# DM2080_Connector_B.net
KiCad netlist of a schematic drawn in Altium Designer
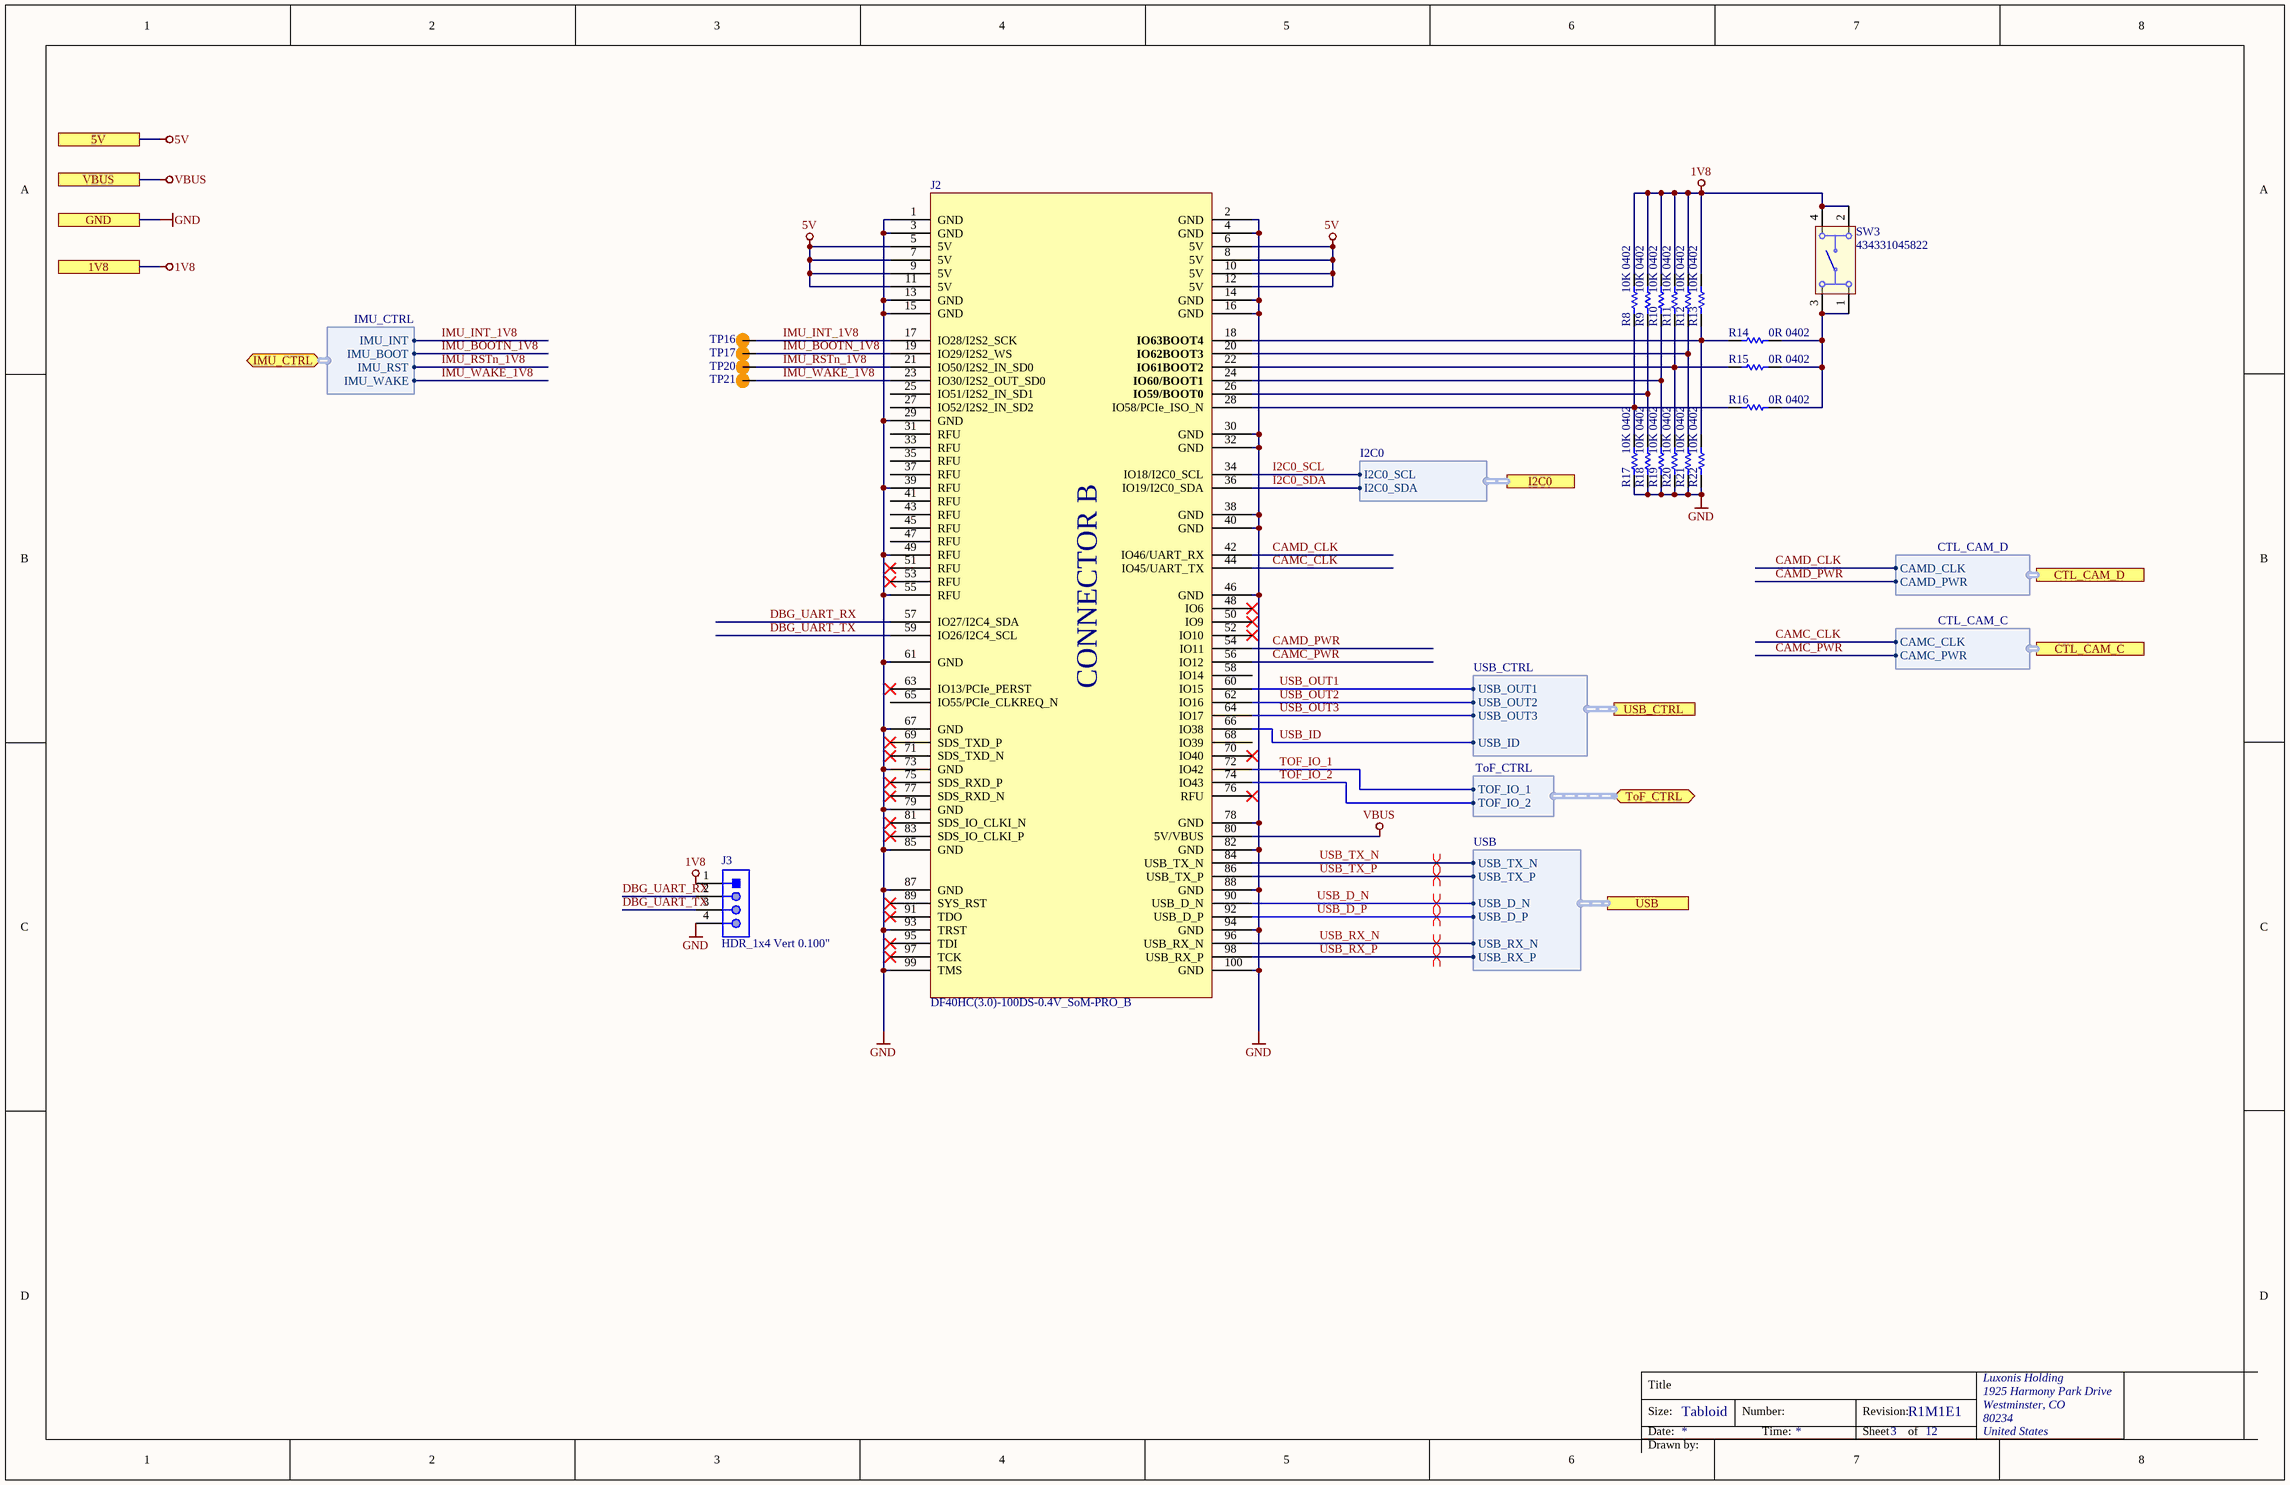
[diagram p0: DM2080_Connector_B.SchDoc]

(export (version "E")
  (design (tool "Eeschema 10.0.6"))
  (components
    (comp (ref "J2")
      (value "DF40HC(3.0)-100DS-0.4V_SoM-PRO_B")
      (footprint "CON_B_BW2099_SoM_DF40HC-3.0-100DS-0.4V_minpad")
      (description "OAK-SoM-Pro base board conn. B")
      (libsource (lib "Luxonis LLC") (part "DF40HC(3.0)-100DS-0.4V_SoM-PRO_B"))
    )
    (comp (ref "J3")
      (value "HDR_1x4 Vert 0.100\"")
      (footprint "LuxonisMaster:61300411121")
      (description "CONN HEADER VERT 4POS 2.54MM  Connector Header Through Hole 4 position 0.100\" (2.54mm)")
      (libsource (lib "LuxonisMaster") (part "61300411121"))
    )
    (comp (ref "R8")
      (value "10K 0402")
      (footprint "RES_Altium_Vault_Generic:RESC0402(1005)_L")
      (fields (field (name "TOLERANCE") "1%"))
      (libsource (lib "LuxonisMaster") (part "RC0402FR-1310KL"))
    )
    (comp (ref "R9")
      (value "10K 0402")
      (footprint "RES_Altium_Vault_Generic:RESC0402(1005)_L")
      (fields (field (name "TOLERANCE") "1%"))
      (libsource (lib "LuxonisMaster") (part "RC0402FR-1310KL"))
    )
    (comp (ref "R10")
      (value "10K 0402")
      (footprint "RES_Altium_Vault_Generic:RESC0402(1005)_L")
      (fields (field (name "TOLERANCE") "1%"))
      (libsource (lib "LuxonisMaster") (part "RC0402FR-1310KL"))
    )
    (comp (ref "R11")
      (value "10K 0402")
      (footprint "RES_Altium_Vault_Generic:RESC0402(1005)_L")
      (fields (field (name "TOLERANCE") "1%"))
      (libsource (lib "LuxonisMaster") (part "RC0402FR-1310KL"))
    )
    (comp (ref "R12")
      (value "10K 0402")
      (footprint "RES_Altium_Vault_Generic:RESC0402(1005)_L")
      (fields (field (name "TOLERANCE") "1%"))
      (libsource (lib "LuxonisMaster") (part "RC0402FR-1310KL"))
    )
    (comp (ref "R13")
      (value "10K 0402")
      (footprint "RES_Altium_Vault_Generic:RESC0402(1005)_L")
      (fields (field (name "TOLERANCE") "1%"))
      (libsource (lib "LuxonisMaster") (part "RC0402FR-1310KL"))
    )
    (comp (ref "R14")
      (value "0R 0402")
      (footprint "RES_Altium_Vault_Generic:RESC0402(1005)_L")
      (description "RES SMD 0 OHM JUMPER 1/16W 0402")
      (fields (field (name "TOLERANCE") "5%"))
      (libsource (lib "LuxonisMaster") (part "CRCW04020000Z0ED"))
    )
    (comp (ref "R15")
      (value "0R 0402")
      (footprint "RES_Altium_Vault_Generic:RESC0402(1005)_L")
      (description "RES SMD 0 OHM JUMPER 1/16W 0402")
      (fields (field (name "TOLERANCE") "5%"))
      (libsource (lib "LuxonisMaster") (part "CRCW04020000Z0ED"))
    )
    (comp (ref "R16")
      (value "0R 0402")
      (footprint "RES_Altium_Vault_Generic:RESC0402(1005)_L")
      (description "RES SMD 0 OHM JUMPER 1/16W 0402")
      (fields (field (name "TOLERANCE") "5%"))
      (libsource (lib "LuxonisMaster") (part "CRCW04020000Z0ED"))
    )
    (comp (ref "R17")
      (value "10K 0402")
      (footprint "RES_Altium_Vault_Generic:RESC0402(1005)_L")
      (fields (field (name "TOLERANCE") "1%"))
      (libsource (lib "LuxonisMaster") (part "RC0402FR-1310KL"))
    )
    (comp (ref "R18")
      (value "10K 0402")
      (footprint "RES_Altium_Vault_Generic:RESC0402(1005)_L")
      (fields (field (name "TOLERANCE") "1%"))
      (libsource (lib "LuxonisMaster") (part "RC0402FR-1310KL"))
    )
    (comp (ref "R19")
      (value "10K 0402")
      (footprint "RES_Altium_Vault_Generic:RESC0402(1005)_L")
      (fields (field (name "TOLERANCE") "1%"))
      (libsource (lib "LuxonisMaster") (part "RC0402FR-1310KL"))
    )
    (comp (ref "R20")
      (value "10K 0402")
      (footprint "RES_Altium_Vault_Generic:RESC0402(1005)_L")
      (fields (field (name "TOLERANCE") "1%"))
      (libsource (lib "LuxonisMaster") (part "RC0402FR-1310KL"))
    )
    (comp (ref "R21")
      (value "10K 0402")
      (footprint "RES_Altium_Vault_Generic:RESC0402(1005)_L")
      (fields (field (name "TOLERANCE") "1%"))
      (libsource (lib "LuxonisMaster") (part "RC0402FR-1310KL"))
    )
    (comp (ref "R22")
      (value "10K 0402")
      (footprint "RES_Altium_Vault_Generic:RESC0402(1005)_L")
      (fields (field (name "TOLERANCE") "1%"))
      (libsource (lib "LuxonisMaster") (part "RC0402FR-1310KL"))
    )
    (comp (ref "SW3")
      (value "434331045822")
      (footprint "434331045822")
      (libsource (lib "Luxonis LLC") (part "WE-TACT-SW-4"))
    )
    (comp (ref "TP16")
      (value "TP100_200_NS")
      (footprint "LuxonisMaster:TP100_200_NS")
      (libsource (lib "LuxonisMaster") (part "TEST_POINT"))
    )
    (comp (ref "TP17")
      (value "TP100_200_NS")
      (footprint "LuxonisMaster:TP100_200_NS")
      (libsource (lib "LuxonisMaster") (part "TEST_POINT"))
    )
    (comp (ref "TP20")
      (value "TP100_200_NS")
      (footprint "LuxonisMaster:TP100_200_NS")
      (libsource (lib "LuxonisMaster") (part "TEST_POINT"))
    )
    (comp (ref "TP21")
      (value "TP100_200_NS")
      (footprint "LuxonisMaster:TP100_200_NS")
      (libsource (lib "LuxonisMaster") (part "TEST_POINT"))
    )
  )
  (nets
    (net (code "8") (name "/CAMC_CLK") (class "Default")
      (node (ref "J2") (pin "44") (pinfunction "IO45/UART_TX_44") (pintype "passive"))
    )
    (net (code "9") (name "/CAMC_PWR") (class "Default")
      (node (ref "J2") (pin "56") (pinfunction "IO12_56") (pintype "passive"))
    )
    (net (code "10") (name "/CAMD_CLK") (class "Default")
      (node (ref "J2") (pin "42") (pinfunction "IO46/UART_RX_42") (pintype "passive"))
    )
    (net (code "11") (name "/CAMD_PWR") (class "Default")
      (node (ref "J2") (pin "54") (pinfunction "IO11_54") (pintype "passive"))
    )
    (net (code "12") (name "/DBG_UART_RX") (class "Default")
      (node (ref "J2") (pin "57") (pinfunction "IO27/I2C4_SDA_57") (pintype "passive"))
      (node (ref "J3") (pin "2") (pinfunction "2_2") (pintype "passive"))
    )
    (net (code "13") (name "/DBG_UART_TX") (class "Default")
      (node (ref "J2") (pin "59") (pinfunction "IO26/I2C4_SCL_59") (pintype "passive"))
      (node (ref "J3") (pin "3") (pinfunction "3_3") (pintype "passive"))
    )
    (net (code "14") (name "/I2C0_SCL") (class "Default")
      (node (ref "J2") (pin "34") (pinfunction "IO18/I2C0_SCL_34") (pintype "passive"))
    )
    (net (code "15") (name "/I2C0_SDA") (class "Default")
      (node (ref "J2") (pin "36") (pinfunction "IO19/I2C0_SDA_36") (pintype "passive"))
    )
    (net (code "16") (name "/IMU_BOOTN_1V8") (class "Default")
      (node (ref "J2") (pin "19") (pinfunction "IO29/I2S2_WS_19") (pintype "passive"))
      (node (ref "TP17") (pin "1") (pintype "passive"))
    )
    (net (code "17") (name "/IMU_INT_1V8") (class "Default")
      (node (ref "J2") (pin "17") (pinfunction "IO28/I2S2_SCK_17") (pintype "passive"))
      (node (ref "TP16") (pin "1") (pintype "passive"))
    )
    (net (code "18") (name "/IMU_RSTn_1V8") (class "Default")
      (node (ref "J2") (pin "21") (pinfunction "IO50/I2S2_IN_SD0_21") (pintype "passive"))
      (node (ref "TP20") (pin "1") (pintype "passive"))
    )
    (net (code "19") (name "/IMU_WAKE_1V8") (class "Default")
      (node (ref "J2") (pin "23") (pinfunction "IO30/I2S2_OUT_SD0_23") (pintype "passive"))
      (node (ref "TP21") (pin "1") (pintype "passive"))
    )
    (net (code "20") (name "/TOF_IO_1") (class "Default")
      (node (ref "J2") (pin "72") (pinfunction "IO42_72") (pintype "passive"))
    )
    (net (code "21") (name "/TOF_IO_2") (class "Default")
      (node (ref "J2") (pin "74") (pinfunction "IO43_74") (pintype "passive"))
    )
    (net (code "22") (name "/USB_D_N") (class "Default")
      (node (ref "J2") (pin "90") (pinfunction "USB_D_N_90") (pintype "passive"))
    )
    (net (code "23") (name "/USB_D_P") (class "Default")
      (node (ref "J2") (pin "92") (pinfunction "USB_D_P_92") (pintype "passive"))
    )
    (net (code "24") (name "/USB_ID") (class "Default")
      (node (ref "J2") (pin "66") (pinfunction "IO38_66") (pintype "passive"))
    )
    (net (code "25") (name "/USB_OUT1") (class "Default")
      (node (ref "J2") (pin "60") (pinfunction "IO15_60") (pintype "passive"))
    )
    (net (code "26") (name "/USB_OUT2") (class "Default")
      (node (ref "J2") (pin "62") (pinfunction "IO16_62") (pintype "passive"))
    )
    (net (code "27") (name "/USB_OUT3") (class "Default")
      (node (ref "J2") (pin "64") (pinfunction "IO17_64") (pintype "passive"))
    )
    (net (code "28") (name "/USB_RX_N") (class "Default")
      (node (ref "J2") (pin "96") (pinfunction "USB_RX_N_96") (pintype "passive"))
    )
    (net (code "29") (name "/USB_RX_P") (class "Default")
      (node (ref "J2") (pin "98") (pinfunction "USB_RX_P_98") (pintype "passive"))
    )
    (net (code "30") (name "/USB_TX_N") (class "Default")
      (node (ref "J2") (pin "84") (pinfunction "USB_TX_N_84") (pintype "passive"))
    )
    (net (code "31") (name "/USB_TX_P") (class "Default")
      (node (ref "J2") (pin "86") (pinfunction "USB_TX_P_86") (pintype "passive"))
    )
    (net (code "39") (name "1V8") (class "Default")
      (node (ref "J3") (pin "1") (pinfunction "1_1") (pintype "passive"))
      (node (ref "R10") (pin "2") (pinfunction "2_2") (pintype "passive"))
      (node (ref "R11") (pin "2") (pinfunction "2_2") (pintype "passive"))
      (node (ref "R12") (pin "2") (pinfunction "2_2") (pintype "passive"))
      (node (ref "R13") (pin "2") (pinfunction "2_2") (pintype "passive"))
      (node (ref "R8") (pin "2") (pinfunction "2_2") (pintype "passive"))
      (node (ref "R9") (pin "2") (pinfunction "2_2") (pintype "passive"))
      (node (ref "SW3") (pin "2") (pinfunction "2_2") (pintype "passive"))
      (node (ref "SW3") (pin "4") (pinfunction "4_4") (pintype "passive"))
    )
    (net (code "40") (name "5V") (class "Default")
      (node (ref "J2") (pin "10") (pinfunction "5V_10") (pintype "passive"))
      (node (ref "J2") (pin "11") (pinfunction "5V_11") (pintype "passive"))
      (node (ref "J2") (pin "12") (pinfunction "5V_12") (pintype "passive"))
      (node (ref "J2") (pin "5") (pinfunction "5V_5") (pintype "passive"))
      (node (ref "J2") (pin "6") (pinfunction "5V_6") (pintype "passive"))
      (node (ref "J2") (pin "7") (pinfunction "5V_7") (pintype "passive"))
      (node (ref "J2") (pin "8") (pinfunction "5V_8") (pintype "passive"))
      (node (ref "J2") (pin "9") (pinfunction "5V_9") (pintype "passive"))
    )
    (net (code "41") (name "GND") (class "Default")
      (node (ref "J2") (pin "1") (pinfunction "GND_1") (pintype "passive"))
      (node (ref "J2") (pin "100") (pinfunction "GND_100") (pintype "passive"))
      (node (ref "J2") (pin "13") (pinfunction "GND_13") (pintype "passive"))
      (node (ref "J2") (pin "14") (pinfunction "GND_14") (pintype "passive"))
      (node (ref "J2") (pin "15") (pinfunction "GND_15") (pintype "passive"))
      (node (ref "J2") (pin "16") (pinfunction "GND_16") (pintype "passive"))
      (node (ref "J2") (pin "2") (pinfunction "GND_2") (pintype "passive"))
      (node (ref "J2") (pin "29") (pinfunction "GND_29") (pintype "passive"))
      (node (ref "J2") (pin "3") (pinfunction "GND_3") (pintype "passive"))
      (node (ref "J2") (pin "30") (pinfunction "GND_30") (pintype "passive"))
      (node (ref "J2") (pin "32") (pinfunction "GND_32") (pintype "passive"))
      (node (ref "J2") (pin "38") (pinfunction "GND_38") (pintype "passive"))
      (node (ref "J2") (pin "39") (pinfunction "RFU_39") (pintype "passive"))
      (node (ref "J2") (pin "4") (pinfunction "GND_4") (pintype "passive"))
      (node (ref "J2") (pin "40") (pinfunction "GND_40") (pintype "passive"))
      (node (ref "J2") (pin "46") (pinfunction "GND_46") (pintype "passive"))
      (node (ref "J2") (pin "49") (pinfunction "RFU_49") (pintype "passive"))
      (node (ref "J2") (pin "55") (pinfunction "RFU_55") (pintype "passive"))
      (node (ref "J2") (pin "61") (pinfunction "GND_61") (pintype "passive"))
      (node (ref "J2") (pin "67") (pinfunction "GND_67") (pintype "passive"))
      (node (ref "J2") (pin "73") (pinfunction "GND_73") (pintype "passive"))
      (node (ref "J2") (pin "78") (pinfunction "GND_78") (pintype "passive"))
      (node (ref "J2") (pin "79") (pinfunction "GND_79") (pintype "passive"))
      (node (ref "J2") (pin "82") (pinfunction "GND_82") (pintype "passive"))
      (node (ref "J2") (pin "85") (pinfunction "GND_85") (pintype "passive"))
      (node (ref "J2") (pin "87") (pinfunction "GND_87") (pintype "passive"))
      (node (ref "J2") (pin "88") (pinfunction "GND_88") (pintype "passive"))
      (node (ref "J2") (pin "93") (pinfunction "TRST_93") (pintype "passive"))
      (node (ref "J2") (pin "94") (pinfunction "GND_94") (pintype "passive"))
      (node (ref "J2") (pin "99") (pinfunction "TMS_99") (pintype "passive"))
      (node (ref "J3") (pin "4") (pinfunction "4_4") (pintype "passive"))
      (node (ref "R17") (pin "1") (pinfunction "1_1") (pintype "passive"))
      (node (ref "R18") (pin "1") (pinfunction "1_1") (pintype "passive"))
      (node (ref "R19") (pin "1") (pinfunction "1_1") (pintype "passive"))
      (node (ref "R20") (pin "1") (pinfunction "1_1") (pintype "passive"))
      (node (ref "R21") (pin "1") (pinfunction "1_1") (pintype "passive"))
      (node (ref "R22") (pin "1") (pinfunction "1_1") (pintype "passive"))
    )
    (net (code "42") (name "Net-(J2-IO58{slash}PCIe_ISO_N)") (class "Default")
      (node (ref "J2") (pin "28") (pinfunction "IO58/PCIe_ISO_N_28") (pintype "passive"))
      (node (ref "R16") (pin "2") (pinfunction "2_2") (pintype "passive"))
      (node (ref "R17") (pin "2") (pinfunction "2_2") (pintype "passive"))
      (node (ref "R8") (pin "1") (pinfunction "1_1") (pintype "passive"))
    )
    (net (code "43") (name "Net-(J2-IO59{slash}BOOT0)") (class "Default")
      (node (ref "J2") (pin "26") (pinfunction "IO59/BOOT0_26") (pintype "passive"))
      (node (ref "R18") (pin "2") (pinfunction "2_2") (pintype "passive"))
      (node (ref "R9") (pin "1") (pinfunction "1_1") (pintype "passive"))
    )
    (net (code "44") (name "Net-(J2-IO60{slash}BOOT1)") (class "Default")
      (node (ref "J2") (pin "24") (pinfunction "IO60/BOOT1_24") (pintype "passive"))
      (node (ref "R10") (pin "1") (pinfunction "1_1") (pintype "passive"))
      (node (ref "R19") (pin "2") (pinfunction "2_2") (pintype "passive"))
    )
    (net (code "45") (name "Net-(J2-IO61BOOT2)") (class "Default")
      (node (ref "J2") (pin "22") (pinfunction "IO61BOOT2_22") (pintype "passive"))
      (node (ref "R11") (pin "1") (pinfunction "1_1") (pintype "passive"))
      (node (ref "R15") (pin "2") (pinfunction "2_2") (pintype "passive"))
      (node (ref "R20") (pin "2") (pinfunction "2_2") (pintype "passive"))
    )
    (net (code "46") (name "Net-(J2-IO62BOOT3)") (class "Default")
      (node (ref "J2") (pin "20") (pinfunction "IO62BOOT3_20") (pintype "passive"))
      (node (ref "R12") (pin "1") (pinfunction "1_1") (pintype "passive"))
      (node (ref "R21") (pin "2") (pinfunction "2_2") (pintype "passive"))
    )
    (net (code "47") (name "Net-(J2-IO63BOOT4)") (class "Default")
      (node (ref "J2") (pin "18") (pinfunction "IO63BOOT4_18") (pintype "passive"))
      (node (ref "R13") (pin "1") (pinfunction "1_1") (pintype "passive"))
      (node (ref "R14") (pin "2") (pinfunction "2_2") (pintype "passive"))
      (node (ref "R22") (pin "2") (pinfunction "2_2") (pintype "passive"))
    )
    (net (code "48") (name "Net-(R14-Pad1)") (class "Default")
      (node (ref "R14") (pin "1") (pinfunction "1_1") (pintype "passive"))
      (node (ref "R15") (pin "1") (pinfunction "1_1") (pintype "passive"))
      (node (ref "R16") (pin "1") (pinfunction "1_1") (pintype "passive"))
      (node (ref "SW3") (pin "1") (pinfunction "1_1") (pintype "passive"))
      (node (ref "SW3") (pin "3") (pinfunction "3_3") (pintype "passive"))
    )
    (net (code "49") (name "VBUS") (class "Default")
      (node (ref "J2") (pin "80") (pinfunction "5V/VBUS_80") (pintype "passive"))
    )
    (net (code "50") (name "unconnected-(J2-IO6-Pad48)") (class "Default")
      (node (ref "J2") (pin "48") (pinfunction "IO6_48") (pintype "passive+no_connect"))
    )
    (net (code "51") (name "unconnected-(J2-IO9-Pad50)") (class "Default")
      (node (ref "J2") (pin "50") (pinfunction "IO9_50") (pintype "passive+no_connect"))
    )
    (net (code "52") (name "unconnected-(J2-IO10-Pad52)") (class "Default")
      (node (ref "J2") (pin "52") (pinfunction "IO10_52") (pintype "passive+no_connect"))
    )
    (net (code "53") (name "unconnected-(J2-IO13{slash}PCIe_PERST-Pad63)") (class "Default")
      (node (ref "J2") (pin "63") (pinfunction "IO13/PCIe_PERST_63") (pintype "passive+no_connect"))
    )
    (net (code "54") (name "unconnected-(J2-IO14-Pad58)") (class "Default")
      (node (ref "J2") (pin "58") (pinfunction "IO14_58") (pintype "passive"))
    )
    (net (code "55") (name "unconnected-(J2-IO39-Pad68)") (class "Default")
      (node (ref "J2") (pin "68") (pinfunction "IO39_68") (pintype "passive"))
    )
    (net (code "56") (name "unconnected-(J2-IO40-Pad70)") (class "Default")
      (node (ref "J2") (pin "70") (pinfunction "IO40_70") (pintype "passive+no_connect"))
    )
    (net (code "57") (name "unconnected-(J2-IO51{slash}I2S2_IN_SD1-Pad25)") (class "Default")
      (node (ref "J2") (pin "25") (pinfunction "IO51/I2S2_IN_SD1_25") (pintype "passive"))
    )
    (net (code "58") (name "unconnected-(J2-IO52{slash}I2S2_IN_SD2-Pad27)") (class "Default")
      (node (ref "J2") (pin "27") (pinfunction "IO52/I2S2_IN_SD2_27") (pintype "passive"))
    )
    (net (code "59") (name "unconnected-(J2-IO55{slash}PCIe_CLKREQ_N-Pad65)") (class "Default")
      (node (ref "J2") (pin "65") (pinfunction "IO55/PCIe_CLKREQ_N_65") (pintype "passive"))
    )
    (net (code "60") (name "unconnected-(J2-RFU-Pad31)") (class "Default")
      (node (ref "J2") (pin "31") (pinfunction "RFU_31") (pintype "passive"))
    )
    (net (code "61") (name "unconnected-(J2-RFU-Pad33)") (class "Default")
      (node (ref "J2") (pin "33") (pinfunction "RFU_33") (pintype "passive"))
    )
    (net (code "62") (name "unconnected-(J2-RFU-Pad35)") (class "Default")
      (node (ref "J2") (pin "35") (pinfunction "RFU_35") (pintype "passive"))
    )
    (net (code "63") (name "unconnected-(J2-RFU-Pad37)") (class "Default")
      (node (ref "J2") (pin "37") (pinfunction "RFU_37") (pintype "passive"))
    )
    (net (code "64") (name "unconnected-(J2-RFU-Pad41)") (class "Default")
      (node (ref "J2") (pin "41") (pinfunction "RFU_41") (pintype "passive"))
    )
    (net (code "65") (name "unconnected-(J2-RFU-Pad43)") (class "Default")
      (node (ref "J2") (pin "43") (pinfunction "RFU_43") (pintype "passive"))
    )
    (net (code "66") (name "unconnected-(J2-RFU-Pad45)") (class "Default")
      (node (ref "J2") (pin "45") (pinfunction "RFU_45") (pintype "passive"))
    )
    (net (code "67") (name "unconnected-(J2-RFU-Pad47)") (class "Default")
      (node (ref "J2") (pin "47") (pinfunction "RFU_47") (pintype "passive"))
    )
    (net (code "68") (name "unconnected-(J2-RFU-Pad51)") (class "Default")
      (node (ref "J2") (pin "51") (pinfunction "RFU_51") (pintype "passive+no_connect"))
    )
    (net (code "69") (name "unconnected-(J2-RFU-Pad53)") (class "Default")
      (node (ref "J2") (pin "53") (pinfunction "RFU_53") (pintype "passive+no_connect"))
    )
    (net (code "70") (name "unconnected-(J2-RFU-Pad76)") (class "Default")
      (node (ref "J2") (pin "76") (pinfunction "RFU_76") (pintype "passive+no_connect"))
    )
    (net (code "71") (name "unconnected-(J2-SDS_IO_CLKI_N-Pad81)") (class "Default")
      (node (ref "J2") (pin "81") (pinfunction "SDS_IO_CLKI_N_81") (pintype "passive+no_connect"))
    )
    (net (code "72") (name "unconnected-(J2-SDS_IO_CLKI_P-Pad83)") (class "Default")
      (node (ref "J2") (pin "83") (pinfunction "SDS_IO_CLKI_P_83") (pintype "passive+no_connect"))
    )
    (net (code "73") (name "unconnected-(J2-SDS_RXD_N-Pad77)") (class "Default")
      (node (ref "J2") (pin "77") (pinfunction "SDS_RXD_N_77") (pintype "passive+no_connect"))
    )
    (net (code "74") (name "unconnected-(J2-SDS_RXD_P-Pad75)") (class "Default")
      (node (ref "J2") (pin "75") (pinfunction "SDS_RXD_P_75") (pintype "passive+no_connect"))
    )
    (net (code "75") (name "unconnected-(J2-SDS_TXD_N-Pad71)") (class "Default")
      (node (ref "J2") (pin "71") (pinfunction "SDS_TXD_N_71") (pintype "passive+no_connect"))
    )
    (net (code "76") (name "unconnected-(J2-SDS_TXD_P-Pad69)") (class "Default")
      (node (ref "J2") (pin "69") (pinfunction "SDS_TXD_P_69") (pintype "passive+no_connect"))
    )
    (net (code "77") (name "unconnected-(J2-SYS_RST-Pad89)") (class "Default")
      (node (ref "J2") (pin "89") (pinfunction "SYS_RST_89") (pintype "passive+no_connect"))
    )
    (net (code "78") (name "unconnected-(J2-TCK-Pad97)") (class "Default")
      (node (ref "J2") (pin "97") (pinfunction "TCK_97") (pintype "passive+no_connect"))
    )
    (net (code "79") (name "unconnected-(J2-TDI-Pad95)") (class "Default")
      (node (ref "J2") (pin "95") (pinfunction "TDI_95") (pintype "passive+no_connect"))
    )
    (net (code "80") (name "unconnected-(J2-TDO-Pad91)") (class "Default")
      (node (ref "J2") (pin "91") (pinfunction "TDO_91") (pintype "passive+no_connect"))
    )
  )
)
